# SCH_555Timer_2021-06-30.net
KiCad netlist of a schematic drawn in EasyEDA
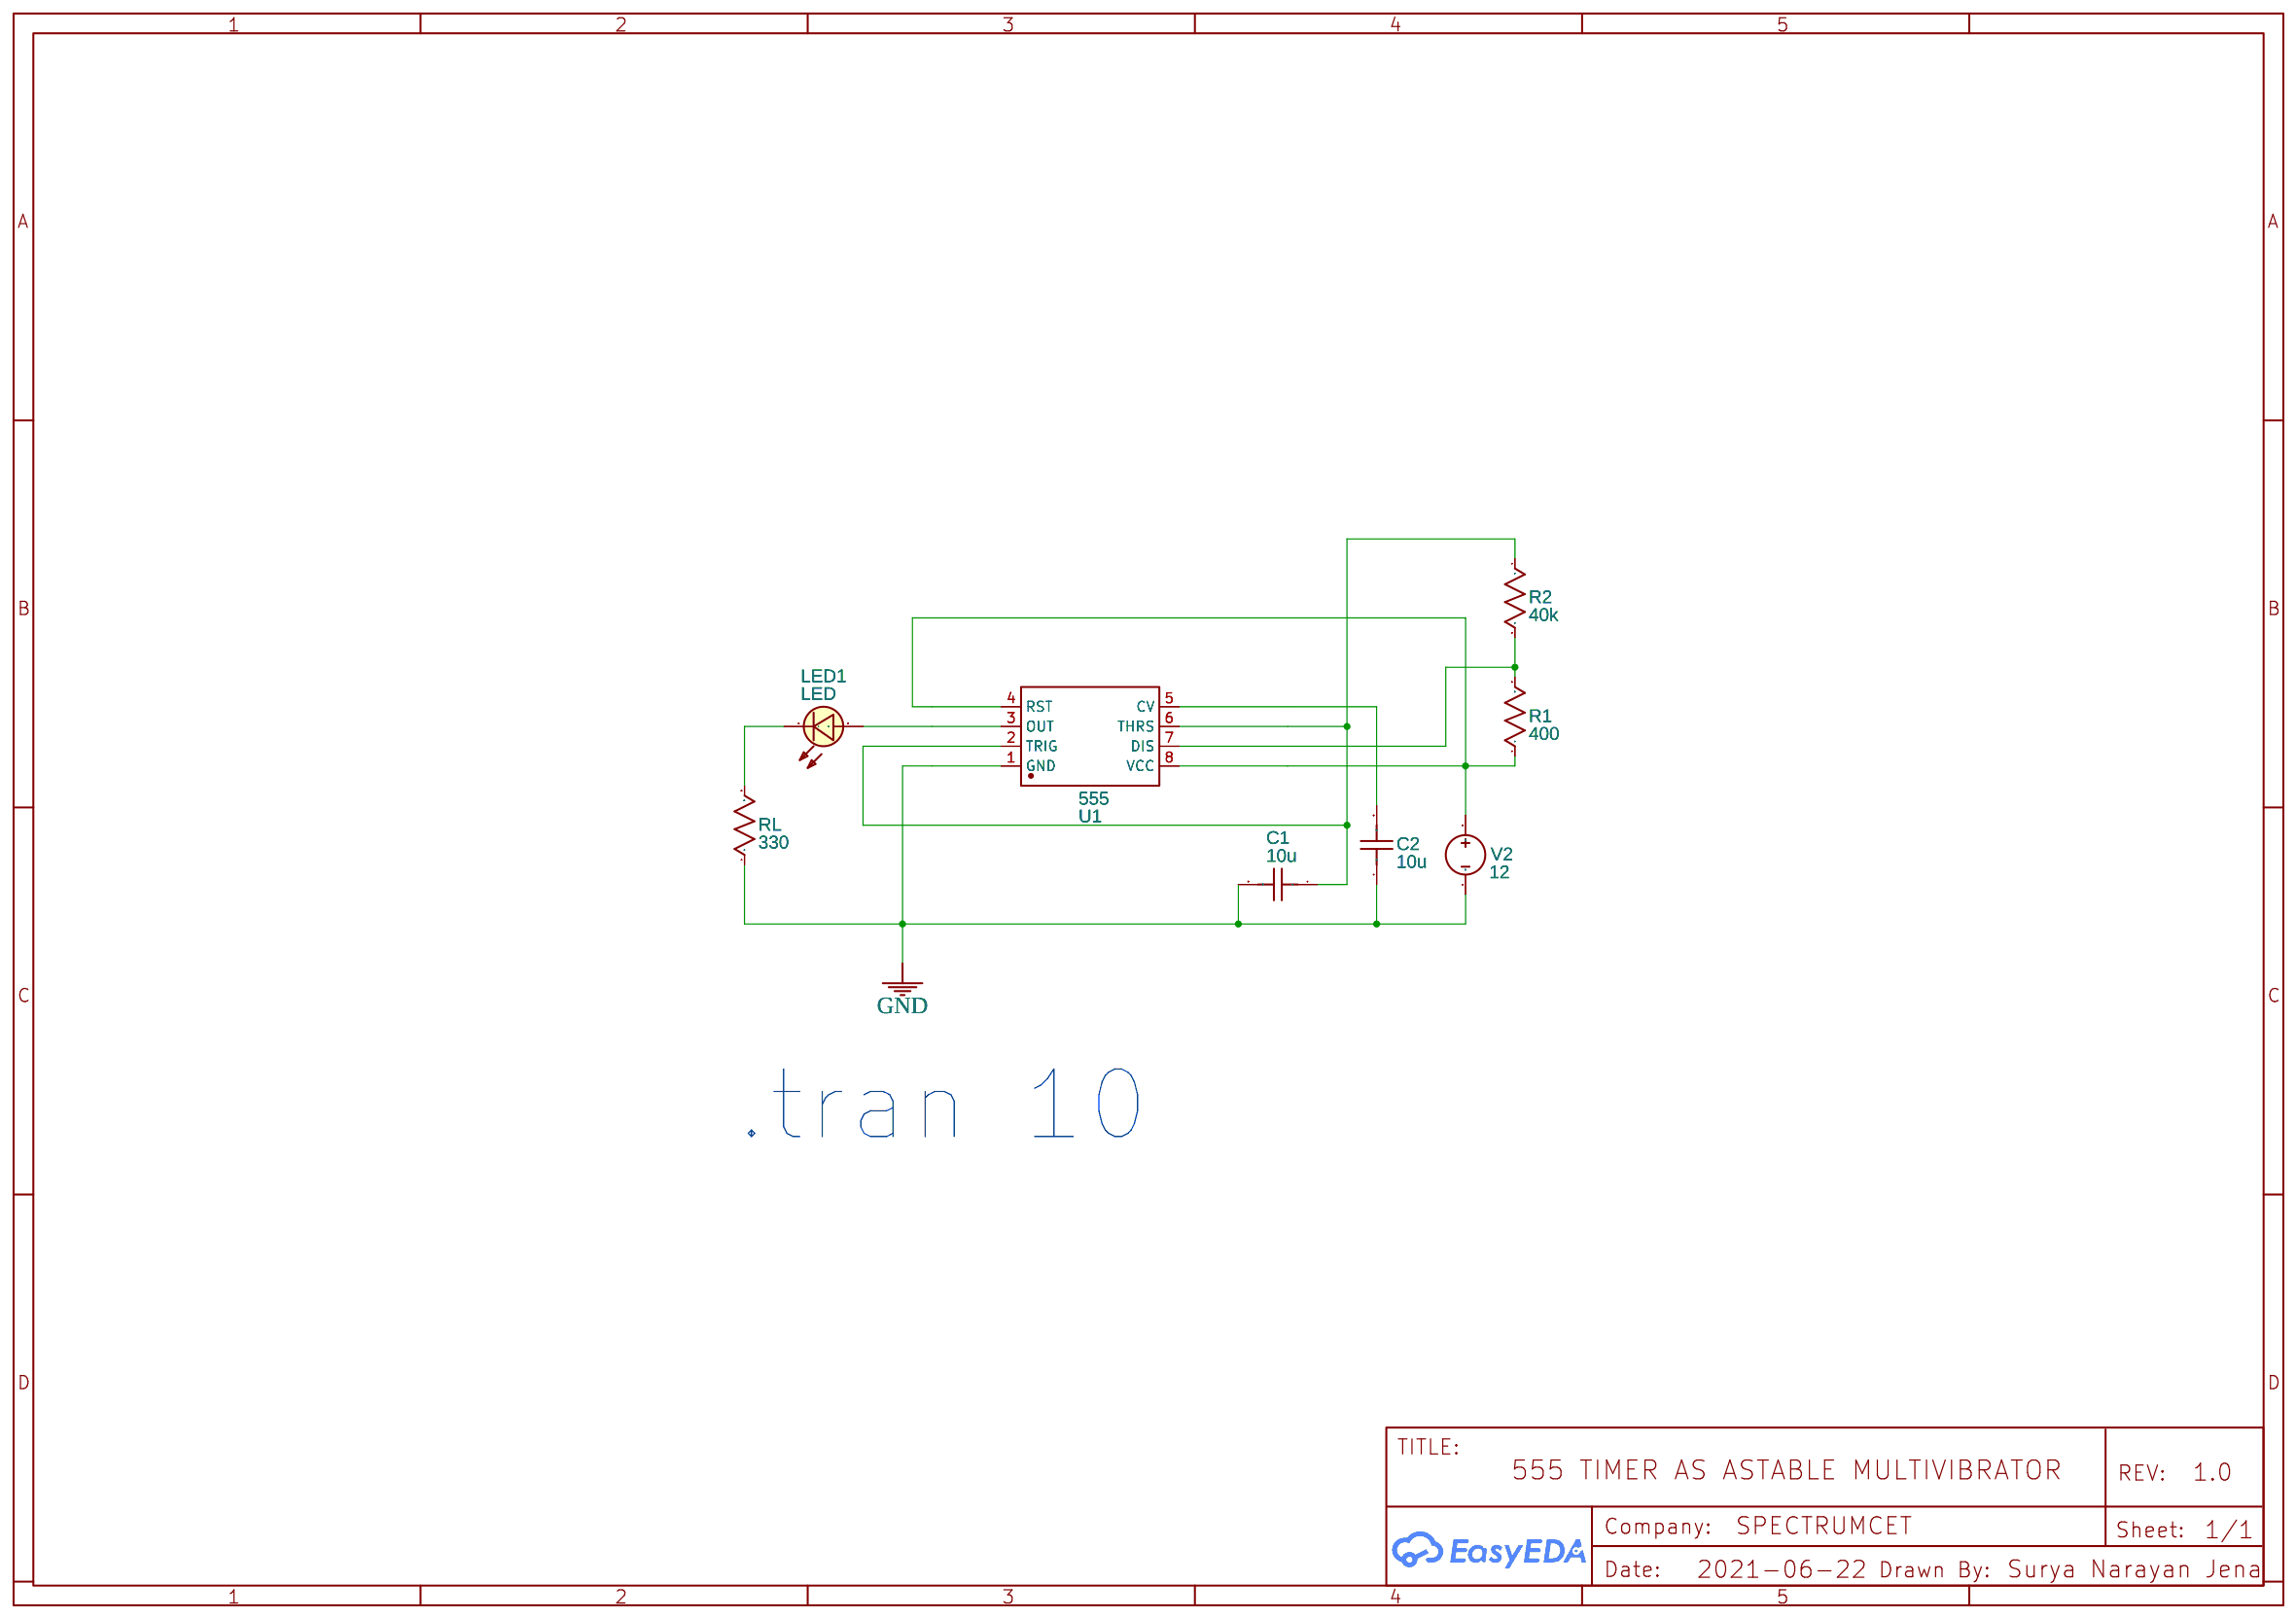
[diagram p0: schematic sheet]

(export (version "E")
  (design (tool "Eeschema 10.0.6"))
  (components
    (comp (ref "C1") (value "10u") (libsource (lib "") (part "C_0603_US")))
    (comp (ref "C2") (value "10u") (libsource (lib "") (part "C_0603_US_1")))
    (comp (ref "LED1") (value "LED") (libsource (lib "") (part "LED")))
    (comp (ref "R1") (value "400") (libsource (lib "") (part "R_0603_US")))
    (comp (ref "R2") (value "40k") (libsource (lib "") (part "R_0603_US_1")))
    (comp (ref "RL") (value "330") (libsource (lib "") (part "R_0603_US_2")))
    (comp (ref "U1") (value "555") (libsource (lib "") (part "555_BJT_EE")))
    (comp (ref "V2") (value "12") (libsource (lib "") (part "VDC")))
  )
  (nets
    (net (code "1") (name "GND") (class "Default")
      (node (ref "C1") (pin "2") (pinfunction "2_2") (pintype "unspecified"))
      (node (ref "C2") (pin "1") (pinfunction "1_1") (pintype "unspecified"))
      (node (ref "RL") (pin "1") (pinfunction "1_1") (pintype "unspecified"))
      (node (ref "U1") (pin "1") (pinfunction "GND_1") (pintype "unspecified"))
      (node (ref "V2") (pin "2") (pinfunction "2_2") (pintype "unspecified"))
    )
    (net (code "2") (name "Net-(LED1-+)") (class "Default")
      (node (ref "LED1") (pin "1") (pinfunction "+_1") (pintype "unspecified"))
      (node (ref "U1") (pin "3") (pinfunction "OUT_3") (pintype "unspecified"))
    )
    (net (code "3") (name "Net-(LED1--)") (class "Default")
      (node (ref "LED1") (pin "2") (pinfunction "-_2") (pintype "unspecified"))
      (node (ref "RL") (pin "2") (pinfunction "2_2") (pintype "unspecified"))
    )
    (net (code "4") (name "Net-(U1-CV)") (class "Default")
      (node (ref "C2") (pin "2") (pinfunction "2_2") (pintype "unspecified"))
      (node (ref "U1") (pin "5") (pinfunction "CV_5") (pintype "unspecified"))
    )
    (net (code "5") (name "Net-(U1-DIS)") (class "Default")
      (node (ref "R1") (pin "2") (pinfunction "2_2") (pintype "unspecified"))
      (node (ref "R2") (pin "2") (pinfunction "2_2") (pintype "unspecified"))
      (node (ref "U1") (pin "7") (pinfunction "DIS_7") (pintype "unspecified"))
    )
    (net (code "6") (name "Net-(U1-RST)") (class "Default")
      (node (ref "R1") (pin "1") (pinfunction "1_1") (pintype "unspecified"))
      (node (ref "U1") (pin "4") (pinfunction "RST_4") (pintype "unspecified"))
      (node (ref "U1") (pin "8") (pinfunction "VCC_8") (pintype "unspecified"))
      (node (ref "V2") (pin "1") (pinfunction "1_1") (pintype "unspecified"))
    )
    (net (code "7") (name "Net-(U1-THRS)") (class "Default")
      (node (ref "C1") (pin "1") (pinfunction "1_1") (pintype "unspecified"))
      (node (ref "R2") (pin "1") (pinfunction "1_1") (pintype "unspecified"))
      (node (ref "U1") (pin "2") (pinfunction "TRIG_2") (pintype "unspecified"))
      (node (ref "U1") (pin "6") (pinfunction "THRS_6") (pintype "unspecified"))
    )
  )
)
